# Pherips.net
KiCad netlist of a schematic drawn in Altium Designer
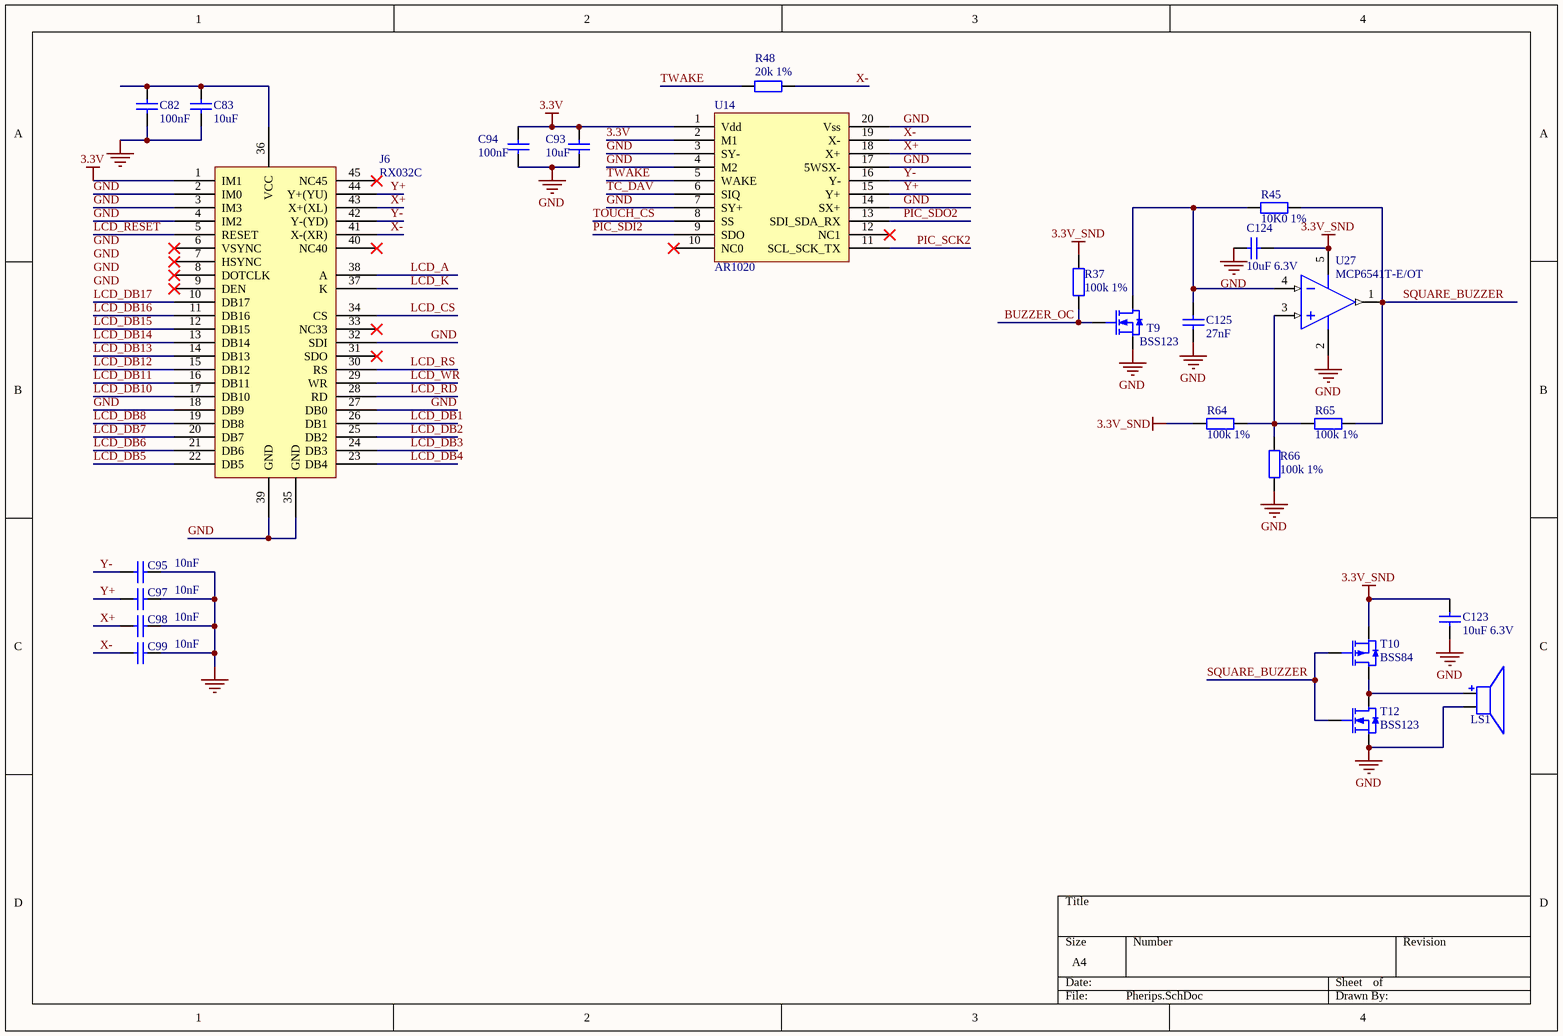
[diagram p0: Pherips.SchDoc]

(export (version "E")
  (design (tool "Eeschema 10.0.6"))
  (components
    (comp (ref "C82")
      (value "100nF")
      (footprint "0603")
      (description "Capacitor")
      (fields (field (name "Comment") "Cap"))
      (libsource (lib "*") (part "Cap"))
    )
    (comp (ref "C83")
      (value "10uF")
      (footprint "0805")
      (description "Capacitor")
      (fields (field (name "Comment") "Cap"))
      (libsource (lib "*") (part "Cap"))
    )
    (comp (ref "C93")
      (value "10uF")
      (footprint "0805")
      (description "Capacitor")
      (fields (field (name "Comment") "Cap"))
      (libsource (lib "*") (part "Cap"))
    )
    (comp (ref "C94")
      (value "100nF")
      (footprint "0603")
      (description "Capacitor")
      (fields (field (name "Comment") "Cap"))
      (libsource (lib "*") (part "Cap"))
    )
    (comp (ref "C95")
      (value "10nF")
      (footprint "0603")
      (description "Capacitor")
      (fields (field (name "Comment") "Cap"))
      (libsource (lib "*") (part "Cap"))
    )
    (comp (ref "C97")
      (value "10nF")
      (footprint "0603")
      (description "Capacitor")
      (fields (field (name "Comment") "Cap"))
      (libsource (lib "*") (part "Cap"))
    )
    (comp (ref "C98")
      (value "10nF")
      (footprint "0603")
      (description "Capacitor")
      (fields (field (name "Comment") "Cap"))
      (libsource (lib "*") (part "Cap"))
    )
    (comp (ref "C99")
      (value "10nF")
      (footprint "0603")
      (description "Capacitor")
      (fields (field (name "Comment") "Cap"))
      (libsource (lib "*") (part "Cap"))
    )
    (comp (ref "C123")
      (value "10uF 6.3V")
      (footprint "0805")
      (description "10uF 0805 10% 6.3V X5R CC0805KKX5R5BB106 (YAG) RoHS")
      (fields (field (name "Comment") "Cap"))
      (libsource (lib "Miscellaneous Devices") (part "Cap"))
    )
    (comp (ref "C124")
      (value "10uF 6.3V")
      (footprint "0805")
      (description "10uF 0805 10% 6.3V X5R CC0805KKX5R5BB106 (YAG) RoHS")
      (fields (field (name "Comment") "Cap"))
      (libsource (lib "Miscellaneous Devices") (part "Cap"))
    )
    (comp (ref "C125")
      (value "27nF")
      (footprint "0603")
      (description "100pF 0603 5% 50V NP0 CC0603JRNP09BN101 (YAG) RoHS")
      (fields (field (name "Comment") "Cap"))
      (libsource (lib "Miscellaneous Devices") (part "Cap"))
    )
    (comp (ref "J6")
      (value "RX032C")
      (footprint "FCI-62684-45210E9ALF-FPC_FFC_BOTTOM")
      (libsource (lib "Thormedr_Sch") (part "RX032C"))
    )
    (comp (ref "LS1")
      (value "Buzzer")
      (footprint "BUZZER_65_45")
      (description "Speaker connector.")
      (libsource (lib "Thormedr_Sch") (part "Buzzer"))
    )
    (comp (ref "R37")
      (value "100k 1%")
      (footprint "0603")
      (description "Resistor")
      (fields (field (name "Comment") "Res"))
      (libsource (lib "*") (part "Res"))
    )
    (comp (ref "R45")
      (value "10K0 1%")
      (footprint "0603")
      (description "10K0 0603 1% CR-03FL7---10K 0.1W (TCL) RoHS")
      (fields (field (name "Comment") "Res2"))
      (libsource (lib "Miscellaneous Devices") (part "Res2"))
    )
    (comp (ref "R48")
      (value "20k 1%")
      (footprint "0603")
      (description "Resistor")
      (libsource (lib "inelteq") (part "Res"))
    )
    (comp (ref "R64")
      (value "100k 1%")
      (footprint "0603")
      (description "Resistor")
      (fields (field (name "Comment") "Res"))
      (libsource (lib "") (part "Res_2"))
    )
    (comp (ref "R65")
      (value "100k 1%")
      (footprint "0603")
      (description "Resistor")
      (fields (field (name "Comment") "Res"))
      (libsource (lib "") (part "Res_1"))
    )
    (comp (ref "R66")
      (value "100k 1%")
      (footprint "0603")
      (description "Resistor")
      (fields (field (name "Comment") "Res"))
      (libsource (lib "*") (part "Res"))
    )
    (comp (ref "T9")
      (value "BSS123")
      (footprint "SOT23")
      (description "N-Channel MOSFET")
      (libsource (lib "*") (part "BSS123"))
    )
    (comp (ref "T10")
      (value "BSS84")
      (footprint "SOT23")
      (description "N-Channel MOSFET")
      (libsource (lib "*") (part "BSS84"))
    )
    (comp (ref "T12")
      (value "BSS123")
      (footprint "SOT23")
      (description "N-Channel MOSFET")
      (libsource (lib "*") (part "BSS123"))
    )
    (comp (ref "U14")
      (value "AR1020")
      (footprint "SSOP20")
      (description "4 wire resistive sensor driver.")
      (libsource (lib "inelteq") (part "AR1020"))
    )
    (comp (ref "U27")
      (value "MCP6541T-E/OT")
      (footprint "SOT-23-OT5_N")
      (description "Push-Pull Output Sub-Microamp Comparator, 5-Pin SOT-23, Extended Temperature, Tape and Reel")
      (libsource (lib "Microchip Linear Devices") (part "MCP6541T-E/OT"))
    )
  )
  (nets
    (net (code "1") (name "/BUZZER_OC") (class "Default")
      (node (ref "R37") (pin "2") (pinfunction "2_2") (pintype "passive"))
      (node (ref "T9") (pin "1") (pinfunction "G_1") (pintype "passive"))
    )
    (net (code "2") (name "/LCD_A") (class "Default")
      (node (ref "J6") (pin "38") (pinfunction "A_38") (pintype "passive"))
    )
    (net (code "3") (name "/LCD_CS") (class "Default")
      (node (ref "J6") (pin "34") (pinfunction "CS_34") (pintype "passive"))
    )
    (net (code "4") (name "/LCD_DB1") (class "Default")
      (node (ref "J6") (pin "26") (pinfunction "DB1_26") (pintype "passive"))
    )
    (net (code "5") (name "/LCD_DB2") (class "Default")
      (node (ref "J6") (pin "25") (pinfunction "DB2_25") (pintype "passive"))
    )
    (net (code "6") (name "/LCD_DB3") (class "Default")
      (node (ref "J6") (pin "24") (pinfunction "DB3_24") (pintype "passive"))
    )
    (net (code "7") (name "/LCD_DB4") (class "Default")
      (node (ref "J6") (pin "23") (pinfunction "DB4_23") (pintype "passive"))
    )
    (net (code "8") (name "/LCD_DB5") (class "Default")
      (node (ref "J6") (pin "22") (pinfunction "DB5_22") (pintype "passive"))
    )
    (net (code "9") (name "/LCD_DB6") (class "Default")
      (node (ref "J6") (pin "21") (pinfunction "DB6_21") (pintype "passive"))
    )
    (net (code "10") (name "/LCD_DB7") (class "Default")
      (node (ref "J6") (pin "20") (pinfunction "DB7_20") (pintype "passive"))
    )
    (net (code "11") (name "/LCD_DB8") (class "Default")
      (node (ref "J6") (pin "19") (pinfunction "DB8_19") (pintype "passive"))
    )
    (net (code "12") (name "/LCD_DB10") (class "Default")
      (node (ref "J6") (pin "17") (pinfunction "DB10_17") (pintype "passive"))
    )
    (net (code "13") (name "/LCD_DB11") (class "Default")
      (node (ref "J6") (pin "16") (pinfunction "DB11_16") (pintype "passive"))
    )
    (net (code "14") (name "/LCD_DB12") (class "Default")
      (node (ref "J6") (pin "15") (pinfunction "DB12_15") (pintype "passive"))
    )
    (net (code "15") (name "/LCD_DB13") (class "Default")
      (node (ref "J6") (pin "14") (pinfunction "DB13_14") (pintype "passive"))
    )
    (net (code "16") (name "/LCD_DB14") (class "Default")
      (node (ref "J6") (pin "13") (pinfunction "DB14_13") (pintype "passive"))
    )
    (net (code "17") (name "/LCD_DB15") (class "Default")
      (node (ref "J6") (pin "12") (pinfunction "DB15_12") (pintype "passive"))
    )
    (net (code "18") (name "/LCD_DB16") (class "Default")
      (node (ref "J6") (pin "11") (pinfunction "DB16_11") (pintype "passive"))
    )
    (net (code "19") (name "/LCD_DB17") (class "Default")
      (node (ref "J6") (pin "10") (pinfunction "DB17_10") (pintype "passive"))
    )
    (net (code "20") (name "/LCD_K") (class "Default")
      (node (ref "J6") (pin "37") (pinfunction "K_37") (pintype "passive"))
    )
    (net (code "21") (name "/LCD_RD") (class "Default")
      (node (ref "J6") (pin "28") (pinfunction "RD_28") (pintype "passive"))
    )
    (net (code "22") (name "/LCD_RESET") (class "Default")
      (node (ref "J6") (pin "5") (pinfunction "RESET_5") (pintype "passive"))
    )
    (net (code "23") (name "/LCD_RS") (class "Default")
      (node (ref "J6") (pin "30") (pinfunction "RS_30") (pintype "passive"))
    )
    (net (code "24") (name "/LCD_WR") (class "Default")
      (node (ref "J6") (pin "29") (pinfunction "WR_29") (pintype "passive"))
    )
    (net (code "25") (name "/PIC_SCK2") (class "Default")
      (node (ref "U14") (pin "11") (pinfunction "SCL_SCK_TX_11") (pintype "passive"))
    )
    (net (code "26") (name "/PIC_SDI2") (class "Default")
      (node (ref "U14") (pin "9") (pinfunction "SDO_9") (pintype "passive"))
    )
    (net (code "27") (name "/PIC_SDO2") (class "Default")
      (node (ref "U14") (pin "13") (pinfunction "SDI_SDA_RX_13") (pintype "passive"))
    )
    (net (code "28") (name "/SQUARE_BUZZER") (class "Default")
      (node (ref "R45") (pin "1") (pinfunction "1_1") (pintype "passive"))
      (node (ref "R65") (pin "2") (pinfunction "2_2") (pintype "passive"))
      (node (ref "T10") (pin "1") (pinfunction "G_1") (pintype "passive"))
      (node (ref "T12") (pin "1") (pinfunction "G_1") (pintype "passive"))
      (node (ref "U27") (pin "1") (pinfunction "OUT_1") (pintype "output"))
    )
    (net (code "29") (name "/TC_DAV") (class "Default")
      (node (ref "U14") (pin "6") (pinfunction "SIQ_6") (pintype "passive"))
    )
    (net (code "30") (name "/TOUCH_CS") (class "Default")
      (node (ref "U14") (pin "8") (pinfunction "SS_8") (pintype "passive"))
    )
    (net (code "31") (name "/TWAKE") (class "Default")
      (node (ref "R48") (pin "2") (pinfunction "2_2") (pintype "passive"))
      (node (ref "U14") (pin "5") (pinfunction "WAKE_5") (pintype "passive"))
    )
    (net (code "32") (name "/X+") (class "Default")
      (node (ref "C98") (pin "1") (pinfunction "1_1") (pintype "passive"))
      (node (ref "J6") (pin "43") (pinfunction "X+(XL)_43") (pintype "passive"))
      (node (ref "U14") (pin "18") (pinfunction "X+_18") (pintype "passive"))
    )
    (net (code "33") (name "/X-") (class "Default")
      (node (ref "C99") (pin "1") (pinfunction "1_1") (pintype "passive"))
      (node (ref "J6") (pin "41") (pinfunction "X-(XR)_41") (pintype "passive"))
      (node (ref "R48") (pin "1") (pinfunction "1_1") (pintype "passive"))
      (node (ref "U14") (pin "19") (pinfunction "X-_19") (pintype "passive"))
    )
    (net (code "34") (name "/Y+") (class "Default")
      (node (ref "C97") (pin "1") (pinfunction "1_1") (pintype "passive"))
      (node (ref "J6") (pin "44") (pinfunction "Y+(YU)_44") (pintype "passive"))
      (node (ref "U14") (pin "15") (pinfunction "Y+_15") (pintype "passive"))
    )
    (net (code "35") (name "/Y-") (class "Default")
      (node (ref "C95") (pin "1") (pinfunction "1_1") (pintype "passive"))
      (node (ref "J6") (pin "42") (pinfunction "Y-(YD)_42") (pintype "passive"))
      (node (ref "U14") (pin "16") (pinfunction "Y-_16") (pintype "passive"))
    )
    (net (code "36") (name "3.3V") (class "Default")
      (node (ref "C93") (pin "2") (pinfunction "2_2") (pintype "passive"))
      (node (ref "C94") (pin "2") (pinfunction "2_2") (pintype "passive"))
      (node (ref "J6") (pin "1") (pinfunction "IM1_1") (pintype "passive"))
      (node (ref "U14") (pin "1") (pinfunction "Vdd_1") (pintype "passive"))
      (node (ref "U14") (pin "2") (pinfunction "M1_2") (pintype "passive"))
    )
    (net (code "37") (name "3.3V_SND") (class "Default")
      (node (ref "C123") (pin "2") (pinfunction "2_2") (pintype "passive"))
      (node (ref "C124") (pin "2") (pinfunction "2_2") (pintype "passive"))
      (node (ref "R37") (pin "1") (pinfunction "1_1") (pintype "passive"))
      (node (ref "R64") (pin "2") (pinfunction "2_2") (pintype "passive"))
      (node (ref "T10") (pin "2") (pinfunction "S_2") (pintype "passive"))
      (node (ref "U27") (pin "5") (pinfunction "VDD_5") (pintype "power_in"))
    )
    (net (code "38") (name "GND") (class "Default")
      (node (ref "C123") (pin "1") (pinfunction "1_1") (pintype "passive"))
      (node (ref "C124") (pin "1") (pinfunction "1_1") (pintype "passive"))
      (node (ref "C125") (pin "1") (pinfunction "1_1") (pintype "passive"))
      (node (ref "C82") (pin "1") (pinfunction "1_1") (pintype "passive"))
      (node (ref "C83") (pin "1") (pinfunction "1_1") (pintype "passive"))
      (node (ref "C93") (pin "1") (pinfunction "1_1") (pintype "passive"))
      (node (ref "C94") (pin "1") (pinfunction "1_1") (pintype "passive"))
      (node (ref "C95") (pin "2") (pinfunction "2_2") (pintype "passive"))
      (node (ref "C97") (pin "2") (pinfunction "2_2") (pintype "passive"))
      (node (ref "C98") (pin "2") (pinfunction "2_2") (pintype "passive"))
      (node (ref "C99") (pin "2") (pinfunction "2_2") (pintype "passive"))
      (node (ref "J6") (pin "18") (pinfunction "DB9_18") (pintype "passive"))
      (node (ref "J6") (pin "2") (pinfunction "IM0_2") (pintype "passive"))
      (node (ref "J6") (pin "27") (pinfunction "DB0_27") (pintype "passive"))
      (node (ref "J6") (pin "3") (pinfunction "IM3_3") (pintype "passive"))
      (node (ref "J6") (pin "32") (pinfunction "SDI_32") (pintype "passive"))
      (node (ref "J6") (pin "35") (pinfunction "GND_35") (pintype "passive"))
      (node (ref "J6") (pin "39") (pinfunction "GND_39") (pintype "passive"))
      (node (ref "J6") (pin "4") (pinfunction "IM2_4") (pintype "passive"))
      (node (ref "LS1") (pin "2") (pinfunction "2_2") (pintype "passive"))
      (node (ref "R66") (pin "2") (pinfunction "2_2") (pintype "passive"))
      (node (ref "T12") (pin "2") (pinfunction "S_2") (pintype "passive"))
      (node (ref "T9") (pin "2") (pinfunction "S_2") (pintype "passive"))
      (node (ref "U14") (pin "14") (pinfunction "SX+_14") (pintype "passive"))
      (node (ref "U14") (pin "17") (pinfunction "5WSX-_17") (pintype "passive"))
      (node (ref "U14") (pin "20") (pinfunction "Vss_20") (pintype "passive"))
      (node (ref "U14") (pin "3") (pinfunction "SY-_3") (pintype "passive"))
      (node (ref "U14") (pin "4") (pinfunction "M2_4") (pintype "passive"))
      (node (ref "U14") (pin "7") (pinfunction "SY+_7") (pintype "passive"))
      (node (ref "U27") (pin "2") (pinfunction "VSS_2") (pintype "power_in"))
    )
    (net (code "39") (name "Net-(J6-VCC)") (class "Default")
      (node (ref "C82") (pin "2") (pinfunction "2_2") (pintype "passive"))
      (node (ref "C83") (pin "2") (pinfunction "2_2") (pintype "passive"))
      (node (ref "J6") (pin "36") (pinfunction "VCC_36") (pintype "passive"))
    )
    (net (code "40") (name "Net-(T9-D)") (class "Default")
      (node (ref "C125") (pin "2") (pinfunction "2_2") (pintype "passive"))
      (node (ref "R45") (pin "2") (pinfunction "2_2") (pintype "passive"))
      (node (ref "T9") (pin "3") (pinfunction "D_3") (pintype "passive"))
      (node (ref "U27") (pin "4") (pinfunction "VIN-_4") (pintype "input"))
    )
    (net (code "41") (name "Net-(T10-D)") (class "Default")
      (node (ref "LS1") (pin "1") (pinfunction "1_1") (pintype "passive"))
      (node (ref "T10") (pin "3") (pinfunction "D_3") (pintype "passive"))
      (node (ref "T12") (pin "3") (pinfunction "D_3") (pintype "passive"))
    )
    (net (code "42") (name "Net-(U27-VIN+)") (class "Default")
      (node (ref "R64") (pin "1") (pinfunction "1_1") (pintype "passive"))
      (node (ref "R65") (pin "1") (pinfunction "1_1") (pintype "passive"))
      (node (ref "R66") (pin "1") (pinfunction "1_1") (pintype "passive"))
      (node (ref "U27") (pin "3") (pinfunction "VIN+_3") (pintype "input"))
    )
    (net (code "43") (name "unconnected-(J6-DEN-Pad9)") (class "Default")
      (node (ref "J6") (pin "9") (pinfunction "DEN_9") (pintype "passive+no_connect"))
    )
    (net (code "44") (name "unconnected-(J6-DOTCLK-Pad8)") (class "Default")
      (node (ref "J6") (pin "8") (pinfunction "DOTCLK_8") (pintype "passive+no_connect"))
    )
    (net (code "45") (name "unconnected-(J6-HSYNC-Pad7)") (class "Default")
      (node (ref "J6") (pin "7") (pinfunction "HSYNC_7") (pintype "passive+no_connect"))
    )
    (net (code "46") (name "unconnected-(J6-NC33-Pad33)") (class "Default")
      (node (ref "J6") (pin "33") (pinfunction "NC33_33") (pintype "passive+no_connect"))
    )
    (net (code "47") (name "unconnected-(J6-NC40-Pad40)") (class "Default")
      (node (ref "J6") (pin "40") (pinfunction "NC40_40") (pintype "passive+no_connect"))
    )
    (net (code "48") (name "unconnected-(J6-NC45-Pad45)") (class "Default")
      (node (ref "J6") (pin "45") (pinfunction "NC45_45") (pintype "passive+no_connect"))
    )
    (net (code "49") (name "unconnected-(J6-SDO-Pad31)") (class "Default")
      (node (ref "J6") (pin "31") (pinfunction "SDO_31") (pintype "passive+no_connect"))
    )
    (net (code "50") (name "unconnected-(J6-VSYNC-Pad6)") (class "Default")
      (node (ref "J6") (pin "6") (pinfunction "VSYNC_6") (pintype "passive+no_connect"))
    )
    (net (code "51") (name "unconnected-(U14-NC0-Pad10)") (class "Default")
      (node (ref "U14") (pin "10") (pinfunction "NC0_10") (pintype "passive+no_connect"))
    )
    (net (code "52") (name "unconnected-(U14-NC1-Pad12)") (class "Default")
      (node (ref "U14") (pin "12") (pinfunction "NC1_12") (pintype "passive+no_connect"))
    )
  )
)
